# blink1_v2c2.net
KiCad netlist of a schematic drawn in EAGLE
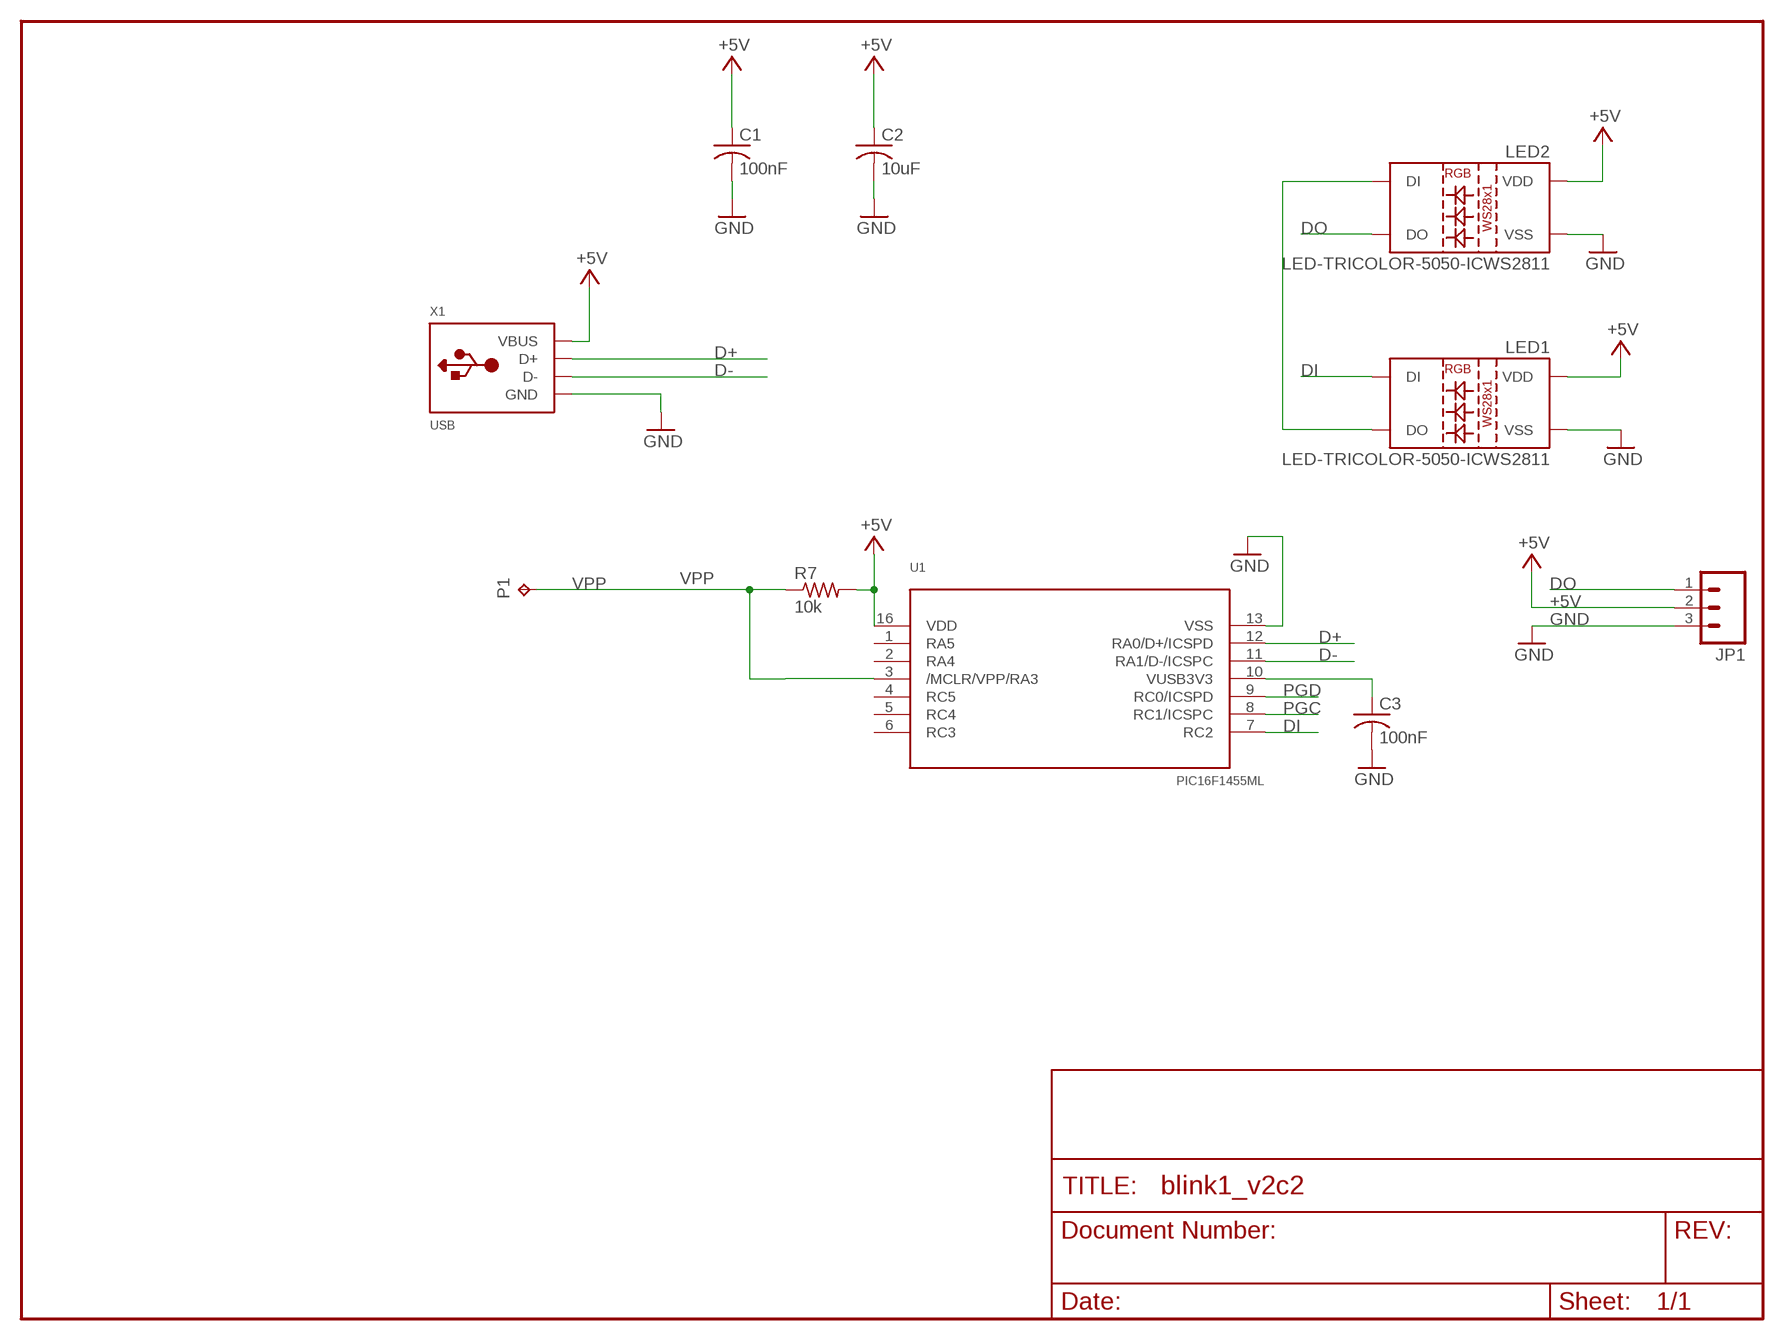
[diagram p0: schematic, sheet 1]

(export (version "E")
  (design (tool "Eeschema 10.0.6"))
  (components
    (comp (ref "C1")
      (value "100nF")
      (footprint "eagle-import:C0603")
      (libsource (lib "eagle-import") (part "C-USC0603"))
    )
    (comp (ref "C2")
      (value "10uF")
      (footprint "eagle-import:C0603")
      (libsource (lib "eagle-import") (part "C-USC0603"))
    )
    (comp (ref "C3")
      (value "100nF")
      (footprint "eagle-import:C0603")
      (libsource (lib "eagle-import") (part "C-USC0603"))
    )
    (comp (ref "JP1")
      (value "M03PTH")
      (footprint "eagle-import:1X03")
      (libsource (lib "eagle-import") (part "M03PTH"))
    )
    (comp (ref "LED1")
      (value "LED-TRICOLOR-5050-ICWS2811")
      (footprint "eagle-import:LED-TRICOLOR-5050-IC")
      (libsource (lib "eagle-import") (part "LED-TRICOLOR-5050-ICWS2811"))
    )
    (comp (ref "LED2")
      (value "LED-TRICOLOR-5050-ICWS2811")
      (footprint "eagle-import:LED-TRICOLOR-5050-IC")
      (libsource (lib "eagle-import") (part "LED-TRICOLOR-5050-ICWS2811"))
    )
    (comp (ref "P1")
      (value "TPTP11SQ")
      (footprint "eagle-import:TP11SQ")
      (libsource (lib "eagle-import") (part "TPTP11SQ"))
    )
    (comp (ref "R7")
      (value "10k")
      (footprint "eagle-import:R0603")
      (libsource (lib "eagle-import") (part "R-US_R0603"))
    )
    (comp (ref "U1")
      (value "PIC16F1455ML")
      (footprint "eagle-import:QFN16_4X4")
      (libsource (lib "eagle-import") (part "PIC16F1455ML"))
    )
    (comp (ref "X1")
      (value "USB")
      (footprint "eagle-import:MOLEX-48037-1000")
      (libsource (lib "eagle-import") (part "USB"))
    )
  )
  (nets
    (net (code "1") (name "+5V") (class "Default")
      (node (ref "C1") (pin "1") (pinfunction "1_1") (pintype "passive"))
      (node (ref "C2") (pin "1") (pinfunction "1_1") (pintype "passive"))
      (node (ref "JP1") (pin "2") (pinfunction "2_2") (pintype "passive"))
      (node (ref "LED1") (pin "3") (pinfunction "VDD_3") (pintype "bidirectional"))
      (node (ref "LED1") (pin "5") (pinfunction "VDD_5") (pintype "bidirectional"))
      (node (ref "LED2") (pin "3") (pinfunction "VDD_3") (pintype "bidirectional"))
      (node (ref "LED2") (pin "5") (pinfunction "VDD_5") (pintype "bidirectional"))
      (node (ref "R7") (pin "2") (pinfunction "2_2") (pintype "passive"))
      (node (ref "U1") (pin "16") (pinfunction "VDD_16") (pintype "bidirectional"))
      (node (ref "X1") (pin "1") (pinfunction "VBUS_1") (pintype "power_in"))
    )
    (net (code "2") (name "/D+") (class "Default")
      (node (ref "U1") (pin "12") (pinfunction "RA0/D+/ICSPD_12") (pintype "bidirectional"))
      (node (ref "X1") (pin "3") (pinfunction "D+_3") (pintype "bidirectional"))
    )
    (net (code "3") (name "/D-") (class "Default")
      (node (ref "U1") (pin "11") (pinfunction "RA1/D-/ICSPC_11") (pintype "bidirectional"))
      (node (ref "X1") (pin "2") (pinfunction "D-_2") (pintype "bidirectional"))
    )
    (net (code "4") (name "/DI") (class "Default")
      (node (ref "LED1") (pin "2") (pinfunction "DI_2") (pintype "bidirectional"))
      (node (ref "U1") (pin "7") (pinfunction "RC2_7") (pintype "bidirectional"))
    )
    (net (code "5") (name "/DO") (class "Default")
      (node (ref "JP1") (pin "1") (pinfunction "1_1") (pintype "passive"))
      (node (ref "LED2") (pin "1") (pinfunction "DO_1") (pintype "bidirectional"))
    )
    (net (code "6") (name "/PGC") (class "Default")
      (node (ref "U1") (pin "8") (pinfunction "RC1/ICSPC_8") (pintype "bidirectional"))
    )
    (net (code "7") (name "/PGD") (class "Default")
      (node (ref "U1") (pin "9") (pinfunction "RC0/ICSPD_9") (pintype "bidirectional"))
    )
    (net (code "8") (name "/VPP") (class "Default")
      (node (ref "P1") (pin "TP") (pinfunction "TP_TP") (pintype "input"))
      (node (ref "R7") (pin "1") (pinfunction "1_1") (pintype "passive"))
      (node (ref "U1") (pin "3") (pinfunction "/MCLR/VPP/RA3_3") (pintype "bidirectional"))
    )
    (net (code "9") (name "GND") (class "Default")
      (node (ref "C1") (pin "2") (pinfunction "2_2") (pintype "passive"))
      (node (ref "C2") (pin "2") (pinfunction "2_2") (pintype "passive"))
      (node (ref "C3") (pin "2") (pinfunction "2_2") (pintype "passive"))
      (node (ref "JP1") (pin "3") (pinfunction "3_3") (pintype "passive"))
      (node (ref "LED1") (pin "6") (pinfunction "VSS_6") (pintype "bidirectional"))
      (node (ref "LED2") (pin "6") (pinfunction "VSS_6") (pintype "bidirectional"))
      (node (ref "U1") (pin "13") (pinfunction "VSS_13") (pintype "bidirectional"))
      (node (ref "X1") (pin "4") (pinfunction "GND_4") (pintype "power_in"))
    )
    (net (code "10") (name "Net-(LED1-DO)") (class "Default")
      (node (ref "LED1") (pin "1") (pinfunction "DO_1") (pintype "bidirectional"))
      (node (ref "LED2") (pin "2") (pinfunction "DI_2") (pintype "bidirectional"))
    )
    (net (code "11") (name "Net-(U1-VUSB3V3)") (class "Default")
      (node (ref "C3") (pin "1") (pinfunction "1_1") (pintype "passive"))
      (node (ref "U1") (pin "10") (pinfunction "VUSB3V3_10") (pintype "bidirectional"))
    )
    (net (code "12") (name "unconnected-(U1-RA4-Pad2)") (class "Default")
      (node (ref "U1") (pin "2") (pinfunction "RA4_2") (pintype "bidirectional"))
    )
    (net (code "13") (name "unconnected-(U1-RA5-Pad1)") (class "Default")
      (node (ref "U1") (pin "1") (pinfunction "RA5_1") (pintype "bidirectional"))
    )
    (net (code "14") (name "unconnected-(U1-RC3-Pad6)") (class "Default")
      (node (ref "U1") (pin "6") (pinfunction "RC3_6") (pintype "bidirectional"))
    )
    (net (code "15") (name "unconnected-(U1-RC4-Pad5)") (class "Default")
      (node (ref "U1") (pin "5") (pinfunction "RC4_5") (pintype "bidirectional"))
    )
    (net (code "16") (name "unconnected-(U1-RC5-Pad4)") (class "Default")
      (node (ref "U1") (pin "4") (pinfunction "RC5_4") (pintype "bidirectional"))
    )
  )
)
